# Aqua.net
KiCad netlist of a schematic drawn in EAGLE
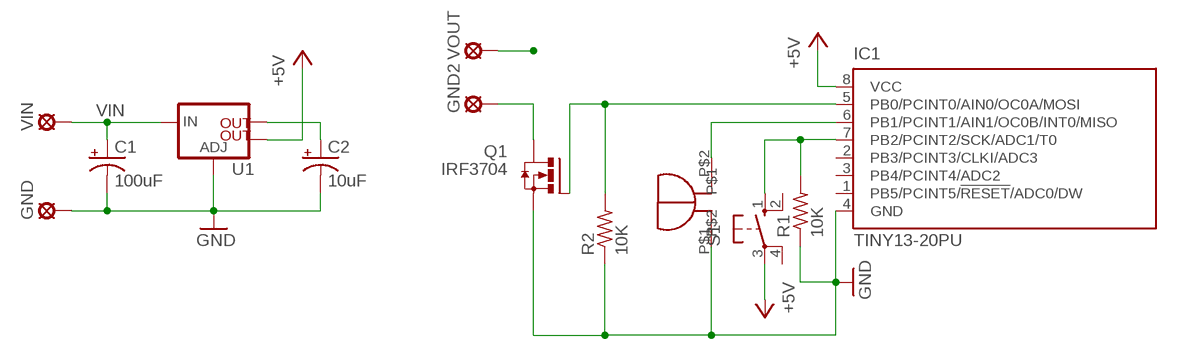
[diagram p0: schematic, sheet 1]

(export (version "E")
  (design (tool "Eeschema 10.0.6"))
  (components
    (comp (ref "C1")
      (value "100uF")
      (footprint "eagle-import:CPOL-RADIAL-10UF-25V")
      (libsource (lib "eagle-import") (part "CAP_POLPTH2"))
    )
    (comp (ref "C2")
      (value "10uF")
      (footprint "eagle-import:CPOL-RADIAL-10UF-25V")
      (libsource (lib "eagle-import") (part "CAP_POLPTH2"))
    )
    (comp (ref "GND")
      (value "LSP11")
      (footprint "eagle-import:LSP11")
      (libsource (lib "eagle-import") (part "LSP11"))
    )
    (comp (ref "GND2")
      (value "LSP11")
      (footprint "eagle-import:LSP11")
      (libsource (lib "eagle-import") (part "LSP11"))
    )
    (comp (ref "IC1")
      (value "TINY13-20PU")
      (footprint "eagle-import:DIL08")
      (fields (field (name "MPN") "ATTINY13-20PU"))
      (libsource (lib "eagle-import") (part "TINY13PU-20"))
    )
    (comp (ref "Q1")
      (value "IRF3704")
      (footprint "eagle-import:TO220AH")
      (libsource (lib "eagle-import") (part "IRF3704"))
    )
    (comp (ref "R1")
      (value "10K")
      (footprint "eagle-import:0207_10")
      (libsource (lib "eagle-import") (part "R-US_0207/10"))
    )
    (comp (ref "R2")
      (value "10K")
      (footprint "eagle-import:0207_10")
      (libsource (lib "eagle-import") (part "R-US_0207/10"))
    )
    (comp (ref "S1")
      (value "10-XX")
      (footprint "eagle-import:B3F-10XX")
      (fields (field (name "MPN") "B3F-1000"))
      (libsource (lib "eagle-import") (part "10-XX"))
    )
    (comp (ref "U$1")
      (value "COMPUTER_BUZZERCOMPUTER_BUZZER")
      (footprint "eagle-import:DGGDG")
      (libsource (lib "eagle-import") (part "COMPUTER_BUZZERCOMPUTER_BUZZER"))
    )
    (comp (ref "U1")
      (value "V_REG_LM1117SOT223")
      (footprint "eagle-import:SOT223")
      (libsource (lib "eagle-import") (part "V_REG_LM1117SOT223"))
    )
    (comp (ref "VIN")
      (value "LSP11")
      (footprint "eagle-import:LSP11")
      (libsource (lib "eagle-import") (part "LSP11"))
    )
    (comp (ref "VOUT")
      (value "LSP11")
      (footprint "eagle-import:LSP11")
      (libsource (lib "eagle-import") (part "LSP11"))
    )
  )
  (nets
    (net (code "1") (name "+5V") (class "Default")
      (node (ref "IC1") (pin "8") (pinfunction "VCC_8") (pintype "power_in"))
      (node (ref "S1") (pin "3") (pinfunction "P_3") (pintype "passive"))
      (node (ref "U1") (pin "4") (pinfunction "OUT_4") (pintype "power_in"))
    )
    (net (code "2") (name "/VIN") (class "Default")
      (node (ref "C1") (pin "1") (pinfunction "+_1") (pintype "passive"))
      (node (ref "U1") (pin "3") (pinfunction "IN_3") (pintype "input"))
      (node (ref "VIN") (pin "MP") (pinfunction "MP_MP") (pintype "passive"))
      (node (ref "VOUT") (pin "MP") (pinfunction "MP_MP") (pintype "passive"))
    )
    (net (code "3") (name "GND") (class "Default")
      (node (ref "C1") (pin "2") (pinfunction "-_2") (pintype "passive"))
      (node (ref "C2") (pin "2") (pinfunction "-_2") (pintype "passive"))
      (node (ref "GND") (pin "MP") (pinfunction "MP_MP") (pintype "passive"))
      (node (ref "IC1") (pin "4") (pinfunction "GND_4") (pintype "power_in"))
      (node (ref "Q1") (pin "E") (pinfunction "S_E") (pintype "passive"))
      (node (ref "R1") (pin "1") (pinfunction "1_1") (pintype "passive"))
      (node (ref "R2") (pin "1") (pinfunction "1_1") (pintype "passive"))
      (node (ref "U$1") (pin "P$1") (pinfunction "P$1_P$1") (pintype "bidirectional"))
      (node (ref "U1") (pin "1") (pinfunction "ADJ_1") (pintype "input"))
    )
    (net (code "4") (name "Net-(C2-+)") (class "Default")
      (node (ref "C2") (pin "1") (pinfunction "+_1") (pintype "passive"))
      (node (ref "U1") (pin "2") (pinfunction "OUT_2") (pintype "power_in"))
    )
    (net (code "5") (name "Net-(IC1-PB0{slash}PCINT0{slash}AIN0{slash}OC0A{slash}MOSI)") (class "Default")
      (node (ref "IC1") (pin "5") (pinfunction "PB0/PCINT0/AIN0/OC0A/MOSI_5") (pintype "bidirectional"))
      (node (ref "Q1") (pin "B") (pinfunction "G_B") (pintype "passive"))
      (node (ref "R2") (pin "2") (pinfunction "2_2") (pintype "passive"))
    )
    (net (code "6") (name "Net-(IC1-PB1{slash}PCINT1{slash}AIN1{slash}OC0B{slash}INT0{slash}MISO)") (class "Default")
      (node (ref "IC1") (pin "6") (pinfunction "PB1/PCINT1/AIN1/OC0B/INT0/MISO_6") (pintype "bidirectional"))
      (node (ref "U$1") (pin "P$2") (pinfunction "P$2_P$2") (pintype "bidirectional"))
    )
    (net (code "7") (name "Net-(IC1-PB2{slash}PCINT2{slash}SCK{slash}ADC1{slash}T0)") (class "Default")
      (node (ref "IC1") (pin "7") (pinfunction "PB2/PCINT2/SCK/ADC1/T0_7") (pintype "bidirectional"))
      (node (ref "R1") (pin "2") (pinfunction "2_2") (pintype "passive"))
      (node (ref "S1") (pin "1") (pinfunction "S_1") (pintype "passive"))
    )
    (net (code "8") (name "Net-(Q1-D)") (class "Default")
      (node (ref "GND2") (pin "MP") (pinfunction "MP_MP") (pintype "passive"))
      (node (ref "Q1") (pin "C") (pinfunction "D_C") (pintype "passive"))
    )
    (net (code "9") (name "unconnected-(IC1-PB3{slash}PCINT3{slash}CLKI{slash}ADC3-Pad2)") (class "Default")
      (node (ref "IC1") (pin "2") (pinfunction "PB3/PCINT3/CLKI/ADC3_2") (pintype "bidirectional"))
    )
    (net (code "10") (name "unconnected-(IC1-PB4{slash}PCINT4{slash}ADC2-Pad3)") (class "Default")
      (node (ref "IC1") (pin "3") (pinfunction "PB4/PCINT4/ADC2_3") (pintype "bidirectional"))
    )
    (net (code "11") (name "unconnected-(IC1-PB5{slash}PCINT5{slash}~{RESET}{slash}ADC0{slash}DW-Pad1)") (class "Default")
      (node (ref "IC1") (pin "1") (pinfunction "PB5/PCINT5/~{RESET}/ADC0/DW_1") (pintype "bidirectional"))
    )
    (net (code "12") (name "unconnected-(S1-P1-Pad4)") (class "Default")
      (node (ref "S1") (pin "4") (pinfunction "P1_4") (pintype "passive"))
    )
    (net (code "13") (name "unconnected-(S1-S1-Pad2)") (class "Default")
      (node (ref "S1") (pin "2") (pinfunction "S1_2") (pintype "passive"))
    )
  )
)
